# CH641P-R0-1v0.net
KiCad netlist of a schematic drawn in Altium Designer
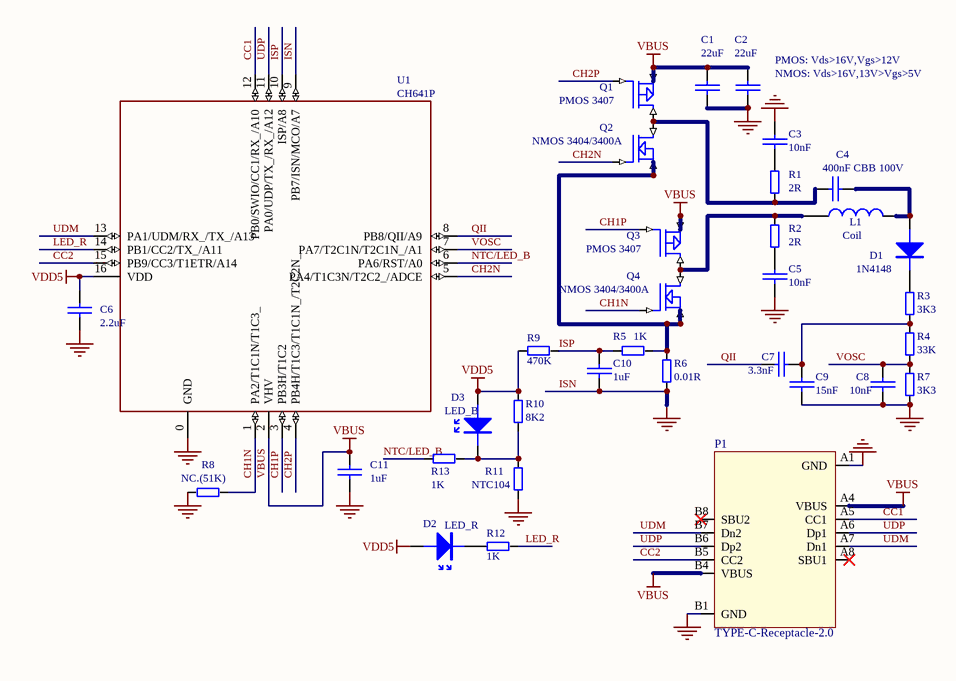
[diagram p0: CH641P-R0-1v0.SchDoc]

(export (version "E")
  (design (tool "Eeschema 10.0.6"))
  (components
    (comp (ref "C1")
      (value "22uF")
      (footprint "1206_C")
      (description "Capacitor")
      (libsource (lib "*") (part "CAP"))
    )
    (comp (ref "C2")
      (value "22uF")
      (footprint "1206_C")
      (description "Capacitor")
      (libsource (lib "*") (part "CAP"))
    )
    (comp (ref "C3")
      (value "10nF")
      (footprint "0603_C")
      (description "Capacitor")
      (libsource (lib "*") (part "CAP"))
    )
    (comp (ref "C4")
      (value "400nF CBB 100V")
      (footprint "SMD2-2.3x2.8_P7.8mm")
      (description "Capacitor")
      (libsource (lib "*") (part "CAP"))
    )
    (comp (ref "C5")
      (value "10nF")
      (footprint "0603_C")
      (description "Capacitor")
      (libsource (lib "*") (part "CAP"))
    )
    (comp (ref "C6")
      (value "2.2uF")
      (footprint "0603_C")
      (description "Capacitor")
      (libsource (lib "*") (part "CAP"))
    )
    (comp (ref "C7")
      (value "3.3nF")
      (footprint "0603_C")
      (description "Capacitor")
      (libsource (lib "*") (part "CAP"))
    )
    (comp (ref "C8")
      (value "10nF")
      (footprint "0603_C")
      (description "Capacitor")
      (libsource (lib "*") (part "CAP"))
    )
    (comp (ref "C9")
      (value "15nF")
      (footprint "0603_C")
      (description "Capacitor")
      (libsource (lib "*") (part "CAP"))
    )
    (comp (ref "C10")
      (value "1uF")
      (footprint "0603_C")
      (description "Capacitor")
      (libsource (lib "*") (part "CAP"))
    )
    (comp (ref "C11")
      (value "1uF")
      (footprint "0603_C")
      (description "Capacitor")
      (libsource (lib "*") (part "CAP"))
    )
    (comp (ref "D1")
      (value "1N4148")
      (footprint "1206+")
      (description "Diode")
      (libsource (lib "*") (part "DIODE"))
    )
    (comp (ref "D2")
      (value "LED_R")
      (footprint "0603+")
      (description "LED")
      (libsource (lib "") (part "LED_1"))
    )
    (comp (ref "D3")
      (value "LED_B")
      (footprint "0603+")
      (description "LED")
      (libsource (lib "*") (part "LED"))
    )
    (comp (ref "L1") (value "Coil") (footprint "SMD2-4x2.5_P17mm") (libsource (lib "*") (part "INDUCTOR")))
    (comp (ref "P1")
      (value "TYPE-C-Receptacle-2.0")
      (footprint "TYPE-C-Receptacle-2.0")
      (description "Type-C USB2.0 母座")
      (libsource (lib "Miscellaneous SCH Lib") (part "TYPE-C-Receptacle-2.0"))
    )
    (comp (ref "Q1")
      (value "PMOS 3407")
      (footprint "SOT-23")
      (description "P-MOSFET")
      (libsource (lib "*") (part "PMOS"))
    )
    (comp (ref "Q2")
      (value "NMOS 3404/3400A")
      (footprint "SOT-23")
      (description "N-MOSFET")
      (libsource (lib "*") (part "NMOS"))
    )
    (comp (ref "Q3")
      (value "PMOS 3407")
      (footprint "SOT-23")
      (description "P-MOSFET")
      (libsource (lib "*") (part "PMOS"))
    )
    (comp (ref "Q4")
      (value "NMOS 3404/3400A")
      (footprint "SOT-23")
      (description "N-MOSFET")
      (libsource (lib "*") (part "NMOS"))
    )
    (comp (ref "R1") (value "2R") (footprint "0603") (libsource (lib "*") (part "R")))
    (comp (ref "R2") (value "2R") (footprint "0603") (libsource (lib "*") (part "R")))
    (comp (ref "R3") (value "3K3") (footprint "0603") (libsource (lib "*") (part "R")))
    (comp (ref "R4") (value "33K") (footprint "0603") (libsource (lib "*") (part "R")))
    (comp (ref "R5") (value "1K") (footprint "0603") (libsource (lib "*") (part "R")))
    (comp (ref "R6") (value "0.01R") (footprint "1206") (libsource (lib "*") (part "R")))
    (comp (ref "R7") (value "3K3") (footprint "0603") (libsource (lib "*") (part "R")))
    (comp (ref "R8") (value "NC.(51K)") (footprint "0603") (libsource (lib "*") (part "R")))
    (comp (ref "R9") (value "470K") (footprint "0603") (libsource (lib "") (part "R_1")))
    (comp (ref "R10") (value "8K2") (footprint "0603") (libsource (lib "*") (part "R")))
    (comp (ref "R11") (value "NTC104") (footprint "0603") (libsource (lib "*") (part "R")))
    (comp (ref "R12") (value "1K") (footprint "0603") (libsource (lib "") (part "R_1")))
    (comp (ref "R13") (value "1K") (footprint "0603") (libsource (lib "*") (part "R")))
    (comp (ref "U1")
      (value "CH641P")
      (footprint "QFN16_3X3")
      (description "RISC-V MCU with PD/ADC/UART/OA, for wireless charging")
      (libsource (lib "*") (part "CH641P"))
    )
  )
  (nets
    (net (code "1") (name "/CC1") (class "Default")
      (node (ref "P1") (pin "A5") (pinfunction "CC1_A5") (pintype "passive"))
      (node (ref "U1") (pin "12") (pinfunction "PB0/SWIO/CC1/RX_/A10_12") (pintype "bidirectional"))
    )
    (net (code "2") (name "/CC2") (class "Default")
      (node (ref "P1") (pin "B5") (pinfunction "CC2_B5") (pintype "passive"))
      (node (ref "U1") (pin "15") (pinfunction "PB9/CC3/T1ETR/A14_15") (pintype "bidirectional"))
    )
    (net (code "3") (name "/CH1N") (class "Default")
      (node (ref "Q4") (pin "1") (pinfunction "G_1") (pintype "input"))
      (node (ref "R8") (pin "1") (pinfunction "1_1") (pintype "passive"))
      (node (ref "U1") (pin "1") (pinfunction "PA2/T1C1N/T1C3__1") (pintype "bidirectional"))
    )
    (net (code "4") (name "/CH1P") (class "Default")
      (node (ref "Q3") (pin "1") (pinfunction "G_1") (pintype "input"))
      (node (ref "U1") (pin "3") (pinfunction "PB3H/T1C2_3") (pintype "bidirectional"))
    )
    (net (code "5") (name "/CH2N") (class "Default")
      (node (ref "Q2") (pin "1") (pinfunction "G_1") (pintype "input"))
      (node (ref "U1") (pin "5") (pinfunction "PA4/T1C3N/T2C2_/ADCE_5") (pintype "bidirectional"))
    )
    (net (code "6") (name "/CH2P") (class "Default")
      (node (ref "Q1") (pin "1") (pinfunction "G_1") (pintype "input"))
      (node (ref "U1") (pin "4") (pinfunction "PB4H/T1C3/T1C1N_/T2C2N__4") (pintype "bidirectional"))
    )
    (net (code "7") (name "/ISP") (class "Default")
      (node (ref "C10") (pin "1") (pinfunction "1_1") (pintype "passive"))
      (node (ref "R5") (pin "1") (pinfunction "1_1") (pintype "passive"))
      (node (ref "R9") (pin "2") (pinfunction "2_2") (pintype "passive"))
      (node (ref "U1") (pin "10") (pinfunction "ISP/A8_10") (pintype "bidirectional"))
    )
    (net (code "8") (name "/LED_R") (class "Default")
      (node (ref "R12") (pin "2") (pinfunction "2_2") (pintype "passive"))
      (node (ref "U1") (pin "14") (pinfunction "PB1/CC2/TX_/A11_14") (pintype "bidirectional"))
    )
    (net (code "9") (name "/NTC{slash}LED_B") (class "Default")
      (node (ref "R13") (pin "1") (pinfunction "1_1") (pintype "passive"))
      (node (ref "U1") (pin "6") (pinfunction "PA6/RST/A0_6") (pintype "bidirectional"))
    )
    (net (code "10") (name "/QII") (class "Default")
      (node (ref "C7") (pin "1") (pinfunction "1_1") (pintype "passive"))
      (node (ref "U1") (pin "8") (pinfunction "PB8/QII/A9_8") (pintype "bidirectional"))
    )
    (net (code "11") (name "/UDM") (class "Default")
      (node (ref "P1") (pin "A7") (pinfunction "Dn1_A7") (pintype "passive"))
      (node (ref "P1") (pin "B7") (pinfunction "Dn2_B7") (pintype "passive"))
      (node (ref "U1") (pin "13") (pinfunction "PA1/UDM/RX_/TX_/A13_13") (pintype "bidirectional"))
    )
    (net (code "12") (name "/UDP") (class "Default")
      (node (ref "P1") (pin "A6") (pinfunction "Dp1_A6") (pintype "passive"))
      (node (ref "P1") (pin "B6") (pinfunction "Dp2_B6") (pintype "passive"))
      (node (ref "U1") (pin "11") (pinfunction "PA0/UDP/TX_/RX_/A12_11") (pintype "bidirectional"))
    )
    (net (code "13") (name "/VOSC") (class "Default")
      (node (ref "C8") (pin "1") (pinfunction "1_1") (pintype "passive"))
      (node (ref "R4") (pin "1") (pinfunction "1_1") (pintype "passive"))
      (node (ref "R7") (pin "2") (pinfunction "2_2") (pintype "passive"))
      (node (ref "U1") (pin "7") (pinfunction "PA7/T2C1N/T2C1N_/A1_7") (pintype "bidirectional"))
    )
    (net (code "14") (name "GND") (class "Default")
      (node (ref "C1") (pin "2") (pinfunction "2_2") (pintype "passive"))
      (node (ref "C10") (pin "2") (pinfunction "2_2") (pintype "passive"))
      (node (ref "C11") (pin "2") (pinfunction "2_2") (pintype "passive"))
      (node (ref "C2") (pin "2") (pinfunction "2_2") (pintype "passive"))
      (node (ref "C3") (pin "1") (pinfunction "1_1") (pintype "passive"))
      (node (ref "C5") (pin "2") (pinfunction "2_2") (pintype "passive"))
      (node (ref "C6") (pin "2") (pinfunction "2_2") (pintype "passive"))
      (node (ref "C8") (pin "2") (pinfunction "2_2") (pintype "passive"))
      (node (ref "C9") (pin "2") (pinfunction "2_2") (pintype "passive"))
      (node (ref "P1") (pin "A1") (pinfunction "GND_A1") (pintype "passive"))
      (node (ref "P1") (pin "B1") (pinfunction "GND_B1") (pintype "passive"))
      (node (ref "R11") (pin "1") (pinfunction "1_1") (pintype "passive"))
      (node (ref "R6") (pin "1") (pinfunction "1_1") (pintype "passive"))
      (node (ref "R7") (pin "1") (pinfunction "1_1") (pintype "passive"))
      (node (ref "R8") (pin "2") (pinfunction "2_2") (pintype "passive"))
      (node (ref "U1") (pin "0") (pinfunction "GND_0") (pintype "power_in"))
      (node (ref "U1") (pin "9") (pinfunction "PB7/ISN/MCO/A7_9") (pintype "bidirectional"))
    )
    (net (code "15") (name "Net-(C3-Pad2)") (class "Default")
      (node (ref "C3") (pin "2") (pinfunction "2_2") (pintype "passive"))
      (node (ref "R1") (pin "2") (pinfunction "2_2") (pintype "passive"))
    )
    (net (code "16") (name "Net-(C5-Pad1)") (class "Default")
      (node (ref "C5") (pin "1") (pinfunction "1_1") (pintype "passive"))
      (node (ref "R2") (pin "1") (pinfunction "1_1") (pintype "passive"))
    )
    (net (code "17") (name "Net-(C7-Pad2)") (class "Default")
      (node (ref "C7") (pin "2") (pinfunction "2_2") (pintype "passive"))
      (node (ref "C9") (pin "1") (pinfunction "1_1") (pintype "passive"))
      (node (ref "R3") (pin "1") (pinfunction "1_1") (pintype "passive"))
      (node (ref "R4") (pin "2") (pinfunction "2_2") (pintype "passive"))
    )
    (net (code "18") (name "Net-(D1-A)") (class "Default")
      (node (ref "C4") (pin "2") (pinfunction "2_2") (pintype "passive"))
      (node (ref "D1") (pin "1") (pinfunction "A_1") (pintype "passive"))
      (node (ref "L1") (pin "2") (pinfunction "2_2") (pintype "passive"))
    )
    (net (code "19") (name "Net-(D1-K)") (class "Default")
      (node (ref "D1") (pin "2") (pinfunction "K_2") (pintype "passive"))
      (node (ref "R3") (pin "2") (pinfunction "2_2") (pintype "passive"))
    )
    (net (code "20") (name "Net-(D2-K)") (class "Default")
      (node (ref "D2") (pin "2") (pinfunction "K_2") (pintype "passive"))
      (node (ref "R12") (pin "1") (pinfunction "1_1") (pintype "passive"))
    )
    (net (code "21") (name "Net-(D3-K)") (class "Default")
      (node (ref "D3") (pin "2") (pinfunction "K_2") (pintype "passive"))
      (node (ref "R10") (pin "2") (pinfunction "2_2") (pintype "passive"))
      (node (ref "R11") (pin "2") (pinfunction "2_2") (pintype "passive"))
      (node (ref "R13") (pin "2") (pinfunction "2_2") (pintype "passive"))
    )
    (net (code "22") (name "Net-(Q1-D)") (class "Default")
      (node (ref "C4") (pin "1") (pinfunction "1_1") (pintype "passive"))
      (node (ref "Q1") (pin "3") (pinfunction "D_3") (pintype "input"))
      (node (ref "Q2") (pin "3") (pinfunction "D_3") (pintype "input"))
      (node (ref "R1") (pin "1") (pinfunction "1_1") (pintype "passive"))
    )
    (net (code "23") (name "Net-(Q2-S)") (class "Default")
      (node (ref "Q2") (pin "2") (pinfunction "S_2") (pintype "input"))
      (node (ref "Q4") (pin "2") (pinfunction "S_2") (pintype "input"))
      (node (ref "R5") (pin "2") (pinfunction "2_2") (pintype "passive"))
      (node (ref "R6") (pin "2") (pinfunction "2_2") (pintype "passive"))
    )
    (net (code "24") (name "Net-(Q3-D)") (class "Default")
      (node (ref "L1") (pin "1") (pinfunction "1_1") (pintype "passive"))
      (node (ref "Q3") (pin "3") (pinfunction "D_3") (pintype "input"))
      (node (ref "Q4") (pin "3") (pinfunction "D_3") (pintype "input"))
      (node (ref "R2") (pin "2") (pinfunction "2_2") (pintype "passive"))
    )
    (net (code "25") (name "VBUS") (class "Default")
      (node (ref "C1") (pin "1") (pinfunction "1_1") (pintype "passive"))
      (node (ref "C11") (pin "1") (pinfunction "1_1") (pintype "passive"))
      (node (ref "C2") (pin "1") (pinfunction "1_1") (pintype "passive"))
      (node (ref "P1") (pin "A4") (pinfunction "VBUS_A4") (pintype "passive"))
      (node (ref "P1") (pin "B4") (pinfunction "VBUS_B4") (pintype "passive"))
      (node (ref "Q1") (pin "2") (pinfunction "S_2") (pintype "input"))
      (node (ref "Q3") (pin "2") (pinfunction "S_2") (pintype "input"))
      (node (ref "U1") (pin "2") (pinfunction "VHV_2") (pintype "power_in"))
    )
    (net (code "26") (name "VDD5") (class "Default")
      (node (ref "C6") (pin "1") (pinfunction "1_1") (pintype "passive"))
      (node (ref "D2") (pin "1") (pinfunction "A_1") (pintype "passive"))
      (node (ref "D3") (pin "1") (pinfunction "A_1") (pintype "passive"))
      (node (ref "R10") (pin "1") (pinfunction "1_1") (pintype "passive"))
      (node (ref "R9") (pin "1") (pinfunction "1_1") (pintype "passive"))
      (node (ref "U1") (pin "16") (pinfunction "VDD_16") (pintype "power_in"))
    )
    (net (code "27") (name "unconnected-(P1-SBU1-PadA8)") (class "Default")
      (node (ref "P1") (pin "A8") (pinfunction "SBU1_A8") (pintype "passive+no_connect"))
    )
    (net (code "28") (name "unconnected-(P1-SBU2-PadB8)") (class "Default")
      (node (ref "P1") (pin "B8") (pinfunction "SBU2_B8") (pintype "passive+no_connect"))
    )
  )
)
